# Motor.net
KiCad netlist of a schematic drawn in Altium Designer
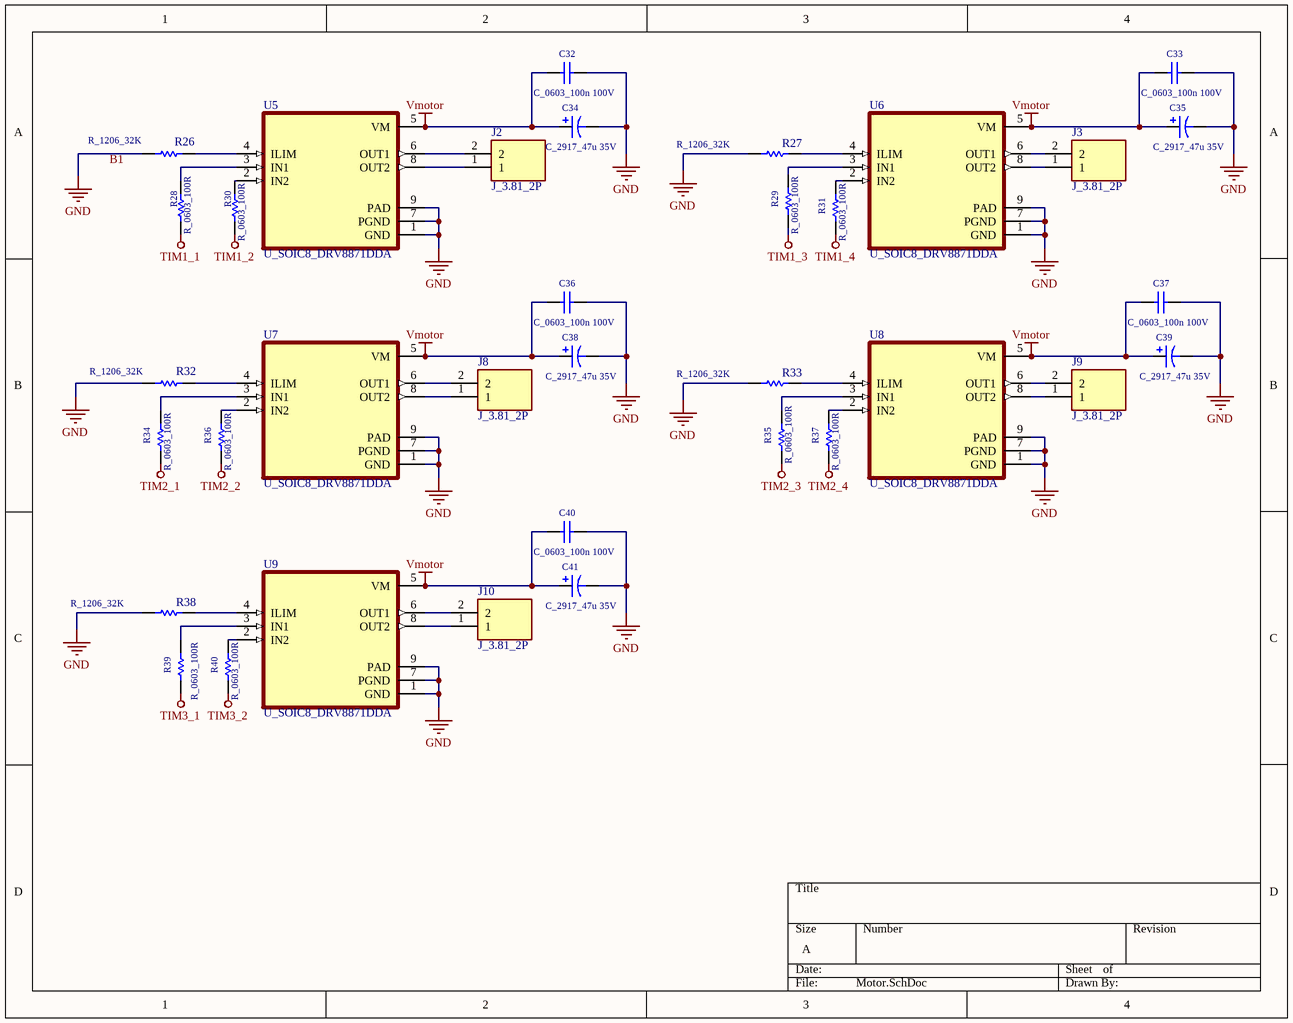
[diagram p0: Motor.SchDoc]

(export (version "E")
  (design (tool "Eeschema 10.0.6"))
  (components
    (comp (ref "C32")
      (value "C_0603_100n 100V")
      (footprint "CAP 0603")
      (description "Capacitor")
      (fields (field (name "PUBLISHER") "Altium Limited"))
      (libsource (lib "HUE") (part "Cap"))
    )
    (comp (ref "C33")
      (value "C_0603_100n 100V")
      (footprint "CAP 0603")
      (description "Capacitor")
      (fields (field (name "PUBLISHER") "Altium Limited"))
      (libsource (lib "HUE") (part "Cap"))
    )
    (comp (ref "C34")
      (value "C_2917_47u 35V")
      (footprint "CAP 2917 TAN")
      (description "Capacitor Tantalium")
      (fields (field (name "PUBLISHER") "Altium Limited"))
      (libsource (lib "HUE") (part "Cap Tantalium"))
    )
    (comp (ref "C35")
      (value "C_2917_47u 35V")
      (footprint "CAP 2917 TAN")
      (description "Capacitor Tantalium")
      (fields (field (name "PUBLISHER") "Altium Limited"))
      (libsource (lib "HUE") (part "Cap Tantalium"))
    )
    (comp (ref "C36")
      (value "C_0603_100n 100V")
      (footprint "CAP 0603")
      (description "Capacitor")
      (fields (field (name "PUBLISHER") "Altium Limited"))
      (libsource (lib "HUE") (part "Cap"))
    )
    (comp (ref "C37")
      (value "C_0603_100n 100V")
      (footprint "CAP 0603")
      (description "Capacitor")
      (fields (field (name "PUBLISHER") "Altium Limited"))
      (libsource (lib "HUE") (part "Cap"))
    )
    (comp (ref "C38")
      (value "C_2917_47u 35V")
      (footprint "CAP 2917 TAN")
      (description "Capacitor Tantalium")
      (fields (field (name "PUBLISHER") "Altium Limited"))
      (libsource (lib "HUE") (part "Cap Tantalium"))
    )
    (comp (ref "C39")
      (value "C_2917_47u 35V")
      (footprint "CAP 2917 TAN")
      (description "Capacitor Tantalium")
      (fields (field (name "PUBLISHER") "Altium Limited"))
      (libsource (lib "HUE") (part "Cap Tantalium"))
    )
    (comp (ref "C40")
      (value "C_0603_100n 100V")
      (footprint "CAP 0603")
      (description "Capacitor")
      (fields (field (name "PUBLISHER") "Altium Limited"))
      (libsource (lib "HUE") (part "Cap"))
    )
    (comp (ref "C41")
      (value "C_2917_47u 35V")
      (footprint "CAP 2917 TAN")
      (description "Capacitor Tantalium")
      (fields (field (name "PUBLISHER") "Altium Limited"))
      (libsource (lib "HUE") (part "Cap Tantalium"))
    )
    (comp (ref "J2")
      (value "J_3.81_2P")
      (footprint "2 Pin PCB TB 3.81")
      (fields (field (name "MF") "CUI Devices") (field (name "MP") "TBP02R1-381-02BE"))
      (libsource (lib "HUE") (part "2 Pin PCB Terminal Block"))
    )
    (comp (ref "J3")
      (value "J_3.81_2P")
      (footprint "2 Pin PCB TB 3.81")
      (fields (field (name "MF") "CUI Devices") (field (name "MP") "TBP02R1-381-02BE"))
      (libsource (lib "HUE") (part "2 Pin PCB Terminal Block"))
    )
    (comp (ref "J8")
      (value "J_3.81_2P")
      (footprint "2 Pin PCB TB 3.81")
      (fields (field (name "MF") "CUI Devices") (field (name "MP") "TBP02R1-381-02BE"))
      (libsource (lib "HUE") (part "2 Pin PCB Terminal Block"))
    )
    (comp (ref "J9")
      (value "J_3.81_2P")
      (footprint "2 Pin PCB TB 3.81")
      (fields (field (name "MF") "CUI Devices") (field (name "MP") "TBP02R1-381-02BE"))
      (libsource (lib "HUE") (part "2 Pin PCB Terminal Block"))
    )
    (comp (ref "J10")
      (value "J_3.81_2P")
      (footprint "2 Pin PCB TB 3.81")
      (fields (field (name "MF") "CUI Devices") (field (name "MP") "TBP02R1-381-02BE"))
      (libsource (lib "HUE") (part "2 Pin PCB Terminal Block"))
    )
    (comp (ref "R26")
      (value "R_1206_32K")
      (footprint "RES 1206")
      (description "Resistor")
      (fields (field (name "PUBLISHER") "Altium Limited"))
      (libsource (lib "HUE") (part "Res"))
    )
    (comp (ref "R27")
      (value "R_1206_32K")
      (footprint "RES 1206")
      (description "Resistor")
      (fields (field (name "PUBLISHER") "Altium Limited"))
      (libsource (lib "HUE") (part "Res"))
    )
    (comp (ref "R28")
      (value "R_0603_100R")
      (footprint "RES 0603")
      (description "Resistor")
      (fields (field (name "PUBLISHER") "Altium Limited"))
      (libsource (lib "HUE") (part "Res"))
    )
    (comp (ref "R29")
      (value "R_0603_100R")
      (footprint "RES 0603")
      (description "Resistor")
      (fields (field (name "PUBLISHER") "Altium Limited"))
      (libsource (lib "HUE") (part "Res"))
    )
    (comp (ref "R30")
      (value "R_0603_100R")
      (footprint "RES 0603")
      (description "Resistor")
      (fields (field (name "PUBLISHER") "Altium Limited"))
      (libsource (lib "HUE") (part "Res"))
    )
    (comp (ref "R31")
      (value "R_0603_100R")
      (footprint "RES 0603")
      (description "Resistor")
      (fields (field (name "PUBLISHER") "Altium Limited"))
      (libsource (lib "HUE") (part "Res"))
    )
    (comp (ref "R32")
      (value "R_1206_32K")
      (footprint "RES 1206")
      (description "Resistor")
      (fields (field (name "PUBLISHER") "Altium Limited"))
      (libsource (lib "HUE") (part "Res"))
    )
    (comp (ref "R33")
      (value "R_1206_32K")
      (footprint "RES 1206")
      (description "Resistor")
      (fields (field (name "PUBLISHER") "Altium Limited"))
      (libsource (lib "HUE") (part "Res"))
    )
    (comp (ref "R34")
      (value "R_0603_100R")
      (footprint "RES 0603")
      (description "Resistor")
      (fields (field (name "PUBLISHER") "Altium Limited"))
      (libsource (lib "HUE") (part "Res"))
    )
    (comp (ref "R35")
      (value "R_0603_100R")
      (footprint "RES 0603")
      (description "Resistor")
      (fields (field (name "PUBLISHER") "Altium Limited"))
      (libsource (lib "HUE") (part "Res"))
    )
    (comp (ref "R36")
      (value "R_0603_100R")
      (footprint "RES 0603")
      (description "Resistor")
      (fields (field (name "PUBLISHER") "Altium Limited"))
      (libsource (lib "HUE") (part "Res"))
    )
    (comp (ref "R37")
      (value "R_0603_100R")
      (footprint "RES 0603")
      (description "Resistor")
      (fields (field (name "PUBLISHER") "Altium Limited"))
      (libsource (lib "HUE") (part "Res"))
    )
    (comp (ref "R38")
      (value "R_1206_32K")
      (footprint "RES 1206")
      (description "Resistor")
      (fields (field (name "PUBLISHER") "Altium Limited"))
      (libsource (lib "HUE") (part "Res"))
    )
    (comp (ref "R39")
      (value "R_0603_100R")
      (footprint "RES 0603")
      (description "Resistor")
      (fields (field (name "PUBLISHER") "Altium Limited"))
      (libsource (lib "HUE") (part "Res"))
    )
    (comp (ref "R40")
      (value "R_0603_100R")
      (footprint "RES 0603")
      (description "Resistor")
      (fields (field (name "PUBLISHER") "Altium Limited"))
      (libsource (lib "HUE") (part "Res"))
    )
    (comp (ref "U5")
      (value "U_SOIC8_DRV8871DDA")
      (footprint "SOIC8")
      (description "45-V, 3.6-A H-bridge motor driver with integrated current sensing 8-SO PowerPAD -40 to 125")
      (fields (field (name "MP") "DRV8871DDA") (field (name "MF") "Texas Instruments"))
      (libsource (lib "HUE") (part "DRV8871DDA"))
    )
    (comp (ref "U6")
      (value "U_SOIC8_DRV8871DDA")
      (footprint "SOIC8")
      (description "45-V, 3.6-A H-bridge motor driver with integrated current sensing 8-SO PowerPAD -40 to 125")
      (fields (field (name "MP") "DRV8871DDA") (field (name "MF") "Texas Instruments"))
      (libsource (lib "HUE") (part "DRV8871DDA"))
    )
    (comp (ref "U7")
      (value "U_SOIC8_DRV8871DDA")
      (footprint "SOIC8")
      (description "45-V, 3.6-A H-bridge motor driver with integrated current sensing 8-SO PowerPAD -40 to 125")
      (fields (field (name "MP") "DRV8871DDA") (field (name "MF") "Texas Instruments"))
      (libsource (lib "HUE") (part "DRV8871DDA"))
    )
    (comp (ref "U8")
      (value "U_SOIC8_DRV8871DDA")
      (footprint "SOIC8")
      (description "45-V, 3.6-A H-bridge motor driver with integrated current sensing 8-SO PowerPAD -40 to 125")
      (fields (field (name "MP") "DRV8871DDA") (field (name "MF") "Texas Instruments"))
      (libsource (lib "HUE") (part "DRV8871DDA"))
    )
    (comp (ref "U9")
      (value "U_SOIC8_DRV8871DDA")
      (footprint "SOIC8")
      (description "45-V, 3.6-A H-bridge motor driver with integrated current sensing 8-SO PowerPAD -40 to 125")
      (fields (field (name "MP") "DRV8871DDA") (field (name "MF") "Texas Instruments"))
      (libsource (lib "HUE") (part "DRV8871DDA"))
    )
  )
  (nets
    (net (code "2") (name "GND") (class "Default")
      (node (ref "C32") (pin "2") (pinfunction "2_2") (pintype "passive"))
      (node (ref "C33") (pin "2") (pinfunction "2_2") (pintype "passive"))
      (node (ref "C34") (pin "2") (pinfunction "2_2") (pintype "passive"))
      (node (ref "C35") (pin "2") (pinfunction "2_2") (pintype "passive"))
      (node (ref "C36") (pin "2") (pinfunction "2_2") (pintype "passive"))
      (node (ref "C37") (pin "2") (pinfunction "2_2") (pintype "passive"))
      (node (ref "C38") (pin "2") (pinfunction "2_2") (pintype "passive"))
      (node (ref "C39") (pin "2") (pinfunction "2_2") (pintype "passive"))
      (node (ref "C40") (pin "2") (pinfunction "2_2") (pintype "passive"))
      (node (ref "C41") (pin "2") (pinfunction "2_2") (pintype "passive"))
      (node (ref "R26") (pin "1") (pinfunction "1_1") (pintype "passive"))
      (node (ref "R27") (pin "1") (pinfunction "1_1") (pintype "passive"))
      (node (ref "R32") (pin "1") (pinfunction "1_1") (pintype "passive"))
      (node (ref "R33") (pin "1") (pinfunction "1_1") (pintype "passive"))
      (node (ref "R38") (pin "1") (pinfunction "1_1") (pintype "passive"))
      (node (ref "U5") (pin "1") (pinfunction "GND_1") (pintype "power_in"))
      (node (ref "U5") (pin "7") (pinfunction "PGND_7") (pintype "power_in"))
      (node (ref "U5") (pin "9") (pinfunction "PAD_9") (pintype "power_in"))
      (node (ref "U6") (pin "1") (pinfunction "GND_1") (pintype "power_in"))
      (node (ref "U6") (pin "7") (pinfunction "PGND_7") (pintype "power_in"))
      (node (ref "U6") (pin "9") (pinfunction "PAD_9") (pintype "power_in"))
      (node (ref "U7") (pin "1") (pinfunction "GND_1") (pintype "power_in"))
      (node (ref "U7") (pin "7") (pinfunction "PGND_7") (pintype "power_in"))
      (node (ref "U7") (pin "9") (pinfunction "PAD_9") (pintype "power_in"))
      (node (ref "U8") (pin "1") (pinfunction "GND_1") (pintype "power_in"))
      (node (ref "U8") (pin "7") (pinfunction "PGND_7") (pintype "power_in"))
      (node (ref "U8") (pin "9") (pinfunction "PAD_9") (pintype "power_in"))
      (node (ref "U9") (pin "1") (pinfunction "GND_1") (pintype "power_in"))
      (node (ref "U9") (pin "7") (pinfunction "PGND_7") (pintype "power_in"))
      (node (ref "U9") (pin "9") (pinfunction "PAD_9") (pintype "power_in"))
    )
    (net (code "3") (name "Net-(U5-ILIM)") (class "Default")
      (node (ref "R26") (pin "2") (pinfunction "2_2") (pintype "passive"))
      (node (ref "U5") (pin "4") (pinfunction "ILIM_4") (pintype "input"))
    )
    (net (code "4") (name "Net-(U5-IN1)") (class "Default")
      (node (ref "R28") (pin "2") (pinfunction "2_2") (pintype "passive"))
      (node (ref "U5") (pin "3") (pinfunction "IN1_3") (pintype "input"))
    )
    (net (code "5") (name "Net-(U5-IN2)") (class "Default")
      (node (ref "R30") (pin "2") (pinfunction "2_2") (pintype "passive"))
      (node (ref "U5") (pin "2") (pinfunction "IN2_2") (pintype "input"))
    )
    (net (code "6") (name "Net-(U5-OUT1)") (class "Default")
      (node (ref "J2") (pin "2") (pinfunction "2_2") (pintype "passive"))
      (node (ref "U5") (pin "6") (pinfunction "OUT1_6") (pintype "output"))
    )
    (net (code "7") (name "Net-(U5-OUT2)") (class "Default")
      (node (ref "J2") (pin "1") (pinfunction "1_1") (pintype "passive"))
      (node (ref "U5") (pin "8") (pinfunction "OUT2_8") (pintype "output"))
    )
    (net (code "8") (name "Net-(U6-ILIM)") (class "Default")
      (node (ref "R27") (pin "2") (pinfunction "2_2") (pintype "passive"))
      (node (ref "U6") (pin "4") (pinfunction "ILIM_4") (pintype "input"))
    )
    (net (code "9") (name "Net-(U6-IN1)") (class "Default")
      (node (ref "R29") (pin "2") (pinfunction "2_2") (pintype "passive"))
      (node (ref "U6") (pin "3") (pinfunction "IN1_3") (pintype "input"))
    )
    (net (code "10") (name "Net-(U6-IN2)") (class "Default")
      (node (ref "R31") (pin "2") (pinfunction "2_2") (pintype "passive"))
      (node (ref "U6") (pin "2") (pinfunction "IN2_2") (pintype "input"))
    )
    (net (code "11") (name "Net-(U6-OUT1)") (class "Default")
      (node (ref "J3") (pin "2") (pinfunction "2_2") (pintype "passive"))
      (node (ref "U6") (pin "6") (pinfunction "OUT1_6") (pintype "output"))
    )
    (net (code "12") (name "Net-(U6-OUT2)") (class "Default")
      (node (ref "J3") (pin "1") (pinfunction "1_1") (pintype "passive"))
      (node (ref "U6") (pin "8") (pinfunction "OUT2_8") (pintype "output"))
    )
    (net (code "13") (name "Net-(U7-ILIM)") (class "Default")
      (node (ref "R32") (pin "2") (pinfunction "2_2") (pintype "passive"))
      (node (ref "U7") (pin "4") (pinfunction "ILIM_4") (pintype "input"))
    )
    (net (code "14") (name "Net-(U7-IN1)") (class "Default")
      (node (ref "R34") (pin "2") (pinfunction "2_2") (pintype "passive"))
      (node (ref "U7") (pin "3") (pinfunction "IN1_3") (pintype "input"))
    )
    (net (code "15") (name "Net-(U7-IN2)") (class "Default")
      (node (ref "R36") (pin "2") (pinfunction "2_2") (pintype "passive"))
      (node (ref "U7") (pin "2") (pinfunction "IN2_2") (pintype "input"))
    )
    (net (code "16") (name "Net-(U7-OUT1)") (class "Default")
      (node (ref "J8") (pin "2") (pinfunction "2_2") (pintype "passive"))
      (node (ref "U7") (pin "6") (pinfunction "OUT1_6") (pintype "output"))
    )
    (net (code "17") (name "Net-(U7-OUT2)") (class "Default")
      (node (ref "J8") (pin "1") (pinfunction "1_1") (pintype "passive"))
      (node (ref "U7") (pin "8") (pinfunction "OUT2_8") (pintype "output"))
    )
    (net (code "18") (name "Net-(U8-ILIM)") (class "Default")
      (node (ref "R33") (pin "2") (pinfunction "2_2") (pintype "passive"))
      (node (ref "U8") (pin "4") (pinfunction "ILIM_4") (pintype "input"))
    )
    (net (code "19") (name "Net-(U8-IN1)") (class "Default")
      (node (ref "R35") (pin "2") (pinfunction "2_2") (pintype "passive"))
      (node (ref "U8") (pin "3") (pinfunction "IN1_3") (pintype "input"))
    )
    (net (code "20") (name "Net-(U8-IN2)") (class "Default")
      (node (ref "R37") (pin "2") (pinfunction "2_2") (pintype "passive"))
      (node (ref "U8") (pin "2") (pinfunction "IN2_2") (pintype "input"))
    )
    (net (code "21") (name "Net-(U8-OUT1)") (class "Default")
      (node (ref "J9") (pin "2") (pinfunction "2_2") (pintype "passive"))
      (node (ref "U8") (pin "6") (pinfunction "OUT1_6") (pintype "output"))
    )
    (net (code "22") (name "Net-(U8-OUT2)") (class "Default")
      (node (ref "J9") (pin "1") (pinfunction "1_1") (pintype "passive"))
      (node (ref "U8") (pin "8") (pinfunction "OUT2_8") (pintype "output"))
    )
    (net (code "23") (name "Net-(U9-ILIM)") (class "Default")
      (node (ref "R38") (pin "2") (pinfunction "2_2") (pintype "passive"))
      (node (ref "U9") (pin "4") (pinfunction "ILIM_4") (pintype "input"))
    )
    (net (code "24") (name "Net-(U9-IN1)") (class "Default")
      (node (ref "R39") (pin "2") (pinfunction "2_2") (pintype "passive"))
      (node (ref "U9") (pin "3") (pinfunction "IN1_3") (pintype "input"))
    )
    (net (code "25") (name "Net-(U9-IN2)") (class "Default")
      (node (ref "R40") (pin "2") (pinfunction "2_2") (pintype "passive"))
      (node (ref "U9") (pin "2") (pinfunction "IN2_2") (pintype "input"))
    )
    (net (code "26") (name "Net-(U9-OUT1)") (class "Default")
      (node (ref "J10") (pin "2") (pinfunction "2_2") (pintype "passive"))
      (node (ref "U9") (pin "6") (pinfunction "OUT1_6") (pintype "output"))
    )
    (net (code "27") (name "Net-(U9-OUT2)") (class "Default")
      (node (ref "J10") (pin "1") (pinfunction "1_1") (pintype "passive"))
      (node (ref "U9") (pin "8") (pinfunction "OUT2_8") (pintype "output"))
    )
    (net (code "28") (name "TIM1_1") (class "Default")
      (node (ref "R28") (pin "1") (pinfunction "1_1") (pintype "passive"))
    )
    (net (code "29") (name "TIM1_2") (class "Default")
      (node (ref "R30") (pin "1") (pinfunction "1_1") (pintype "passive"))
    )
    (net (code "30") (name "TIM1_3") (class "Default")
      (node (ref "R29") (pin "1") (pinfunction "1_1") (pintype "passive"))
    )
    (net (code "31") (name "TIM1_4") (class "Default")
      (node (ref "R31") (pin "1") (pinfunction "1_1") (pintype "passive"))
    )
    (net (code "32") (name "TIM2_1") (class "Default")
      (node (ref "R34") (pin "1") (pinfunction "1_1") (pintype "passive"))
    )
    (net (code "33") (name "TIM2_2") (class "Default")
      (node (ref "R36") (pin "1") (pinfunction "1_1") (pintype "passive"))
    )
    (net (code "34") (name "TIM2_3") (class "Default")
      (node (ref "R35") (pin "1") (pinfunction "1_1") (pintype "passive"))
    )
    (net (code "35") (name "TIM2_4") (class "Default")
      (node (ref "R37") (pin "1") (pinfunction "1_1") (pintype "passive"))
    )
    (net (code "36") (name "TIM3_1") (class "Default")
      (node (ref "R39") (pin "1") (pinfunction "1_1") (pintype "passive"))
    )
    (net (code "37") (name "TIM3_2") (class "Default")
      (node (ref "R40") (pin "1") (pinfunction "1_1") (pintype "passive"))
    )
    (net (code "38") (name "Vmotor") (class "Default")
      (node (ref "C32") (pin "1") (pinfunction "1_1") (pintype "passive"))
      (node (ref "C33") (pin "1") (pinfunction "1_1") (pintype "passive"))
      (node (ref "C34") (pin "1") (pinfunction "1_1") (pintype "passive"))
      (node (ref "C35") (pin "1") (pinfunction "1_1") (pintype "passive"))
      (node (ref "C36") (pin "1") (pinfunction "1_1") (pintype "passive"))
      (node (ref "C37") (pin "1") (pinfunction "1_1") (pintype "passive"))
      (node (ref "C38") (pin "1") (pinfunction "1_1") (pintype "passive"))
      (node (ref "C39") (pin "1") (pinfunction "1_1") (pintype "passive"))
      (node (ref "C40") (pin "1") (pinfunction "1_1") (pintype "passive"))
      (node (ref "C41") (pin "1") (pinfunction "1_1") (pintype "passive"))
      (node (ref "U5") (pin "5") (pinfunction "VM_5") (pintype "power_in"))
      (node (ref "U6") (pin "5") (pinfunction "VM_5") (pintype "power_in"))
      (node (ref "U7") (pin "5") (pinfunction "VM_5") (pintype "power_in"))
      (node (ref "U8") (pin "5") (pinfunction "VM_5") (pintype "power_in"))
      (node (ref "U9") (pin "5") (pinfunction "VM_5") (pintype "power_in"))
    )
  )
)
